# Sheet1.net
KiCad netlist of a schematic drawn in Altium Designer
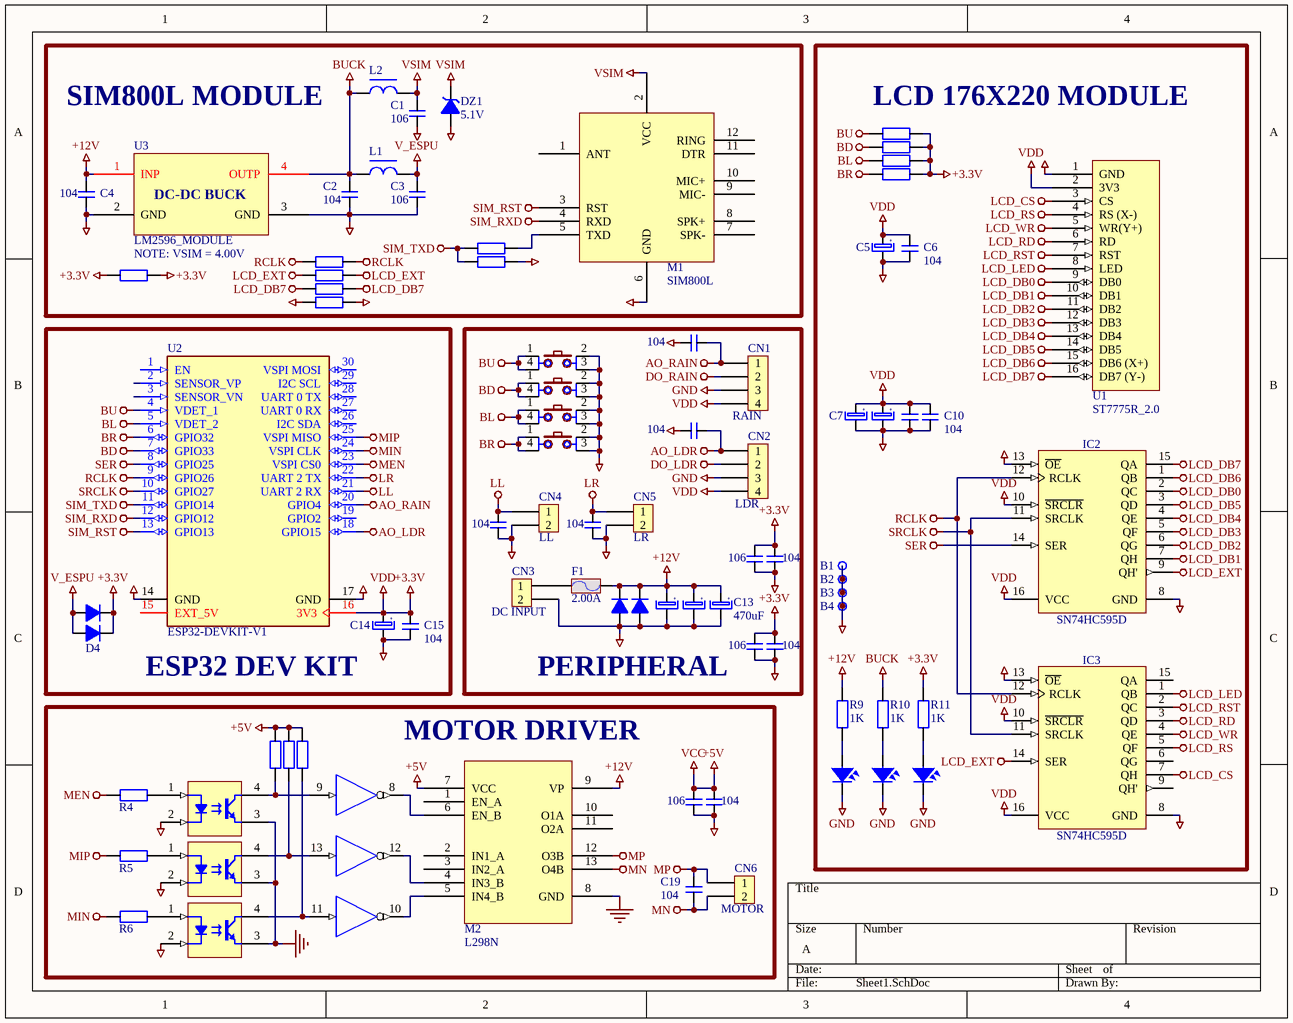
[diagram p0: Sheet1.SchDoc]

(export (version "E")
  (design (tool "Eeschema 10.0.6"))
  (components
    (comp (ref "B1")
      (value "Plated Hole")
      (footprint "MTG300_600")
      (description "Single Terminal Socket")
      (fields (field (name "PART NUMBER") "PLATED_HOLE3.0_PAD6.0") (field (name "AUTHOR") "CERN DEM JLC"))
      (libsource (lib "Eletro-mechanical") (part "Single Terminal Socket"))
    )
    (comp (ref "B2")
      (value "Plated Hole")
      (footprint "MTG300_600")
      (description "Single Terminal Socket")
      (fields (field (name "PART NUMBER") "PLATED_HOLE3.0_PAD6.0") (field (name "AUTHOR") "CERN DEM JLC"))
      (libsource (lib "Eletro-mechanical") (part "Single Terminal Socket"))
    )
    (comp (ref "B3")
      (value "Plated Hole")
      (footprint "MTG300_600")
      (description "Single Terminal Socket")
      (fields (field (name "PART NUMBER") "PLATED_HOLE3.0_PAD6.0") (field (name "AUTHOR") "CERN DEM JLC"))
      (libsource (lib "Eletro-mechanical") (part "Single Terminal Socket"))
    )
    (comp (ref "B4")
      (value "Plated Hole")
      (footprint "MTG300_600")
      (description "Single Terminal Socket")
      (fields (field (name "PART NUMBER") "PLATED_HOLE3.0_PAD6.0") (field (name "AUTHOR") "CERN DEM JLC"))
      (libsource (lib "Eletro-mechanical") (part "Single Terminal Socket"))
    )
    (comp (ref "C1")
      (value "106")
      (footprint "CAP-SMD-0805")
      (description "Non-polar capacitor")
      (libsource (lib "Library") (part "Cap-Non-SMD"))
    )
    (comp (ref "C2")
      (value "104")
      (footprint "Cap-Non-150mil")
      (description "Non-polar capacitor")
      (libsource (lib "Library") (part "Cap-Non-Dip"))
    )
    (comp (ref "C3")
      (value "106")
      (footprint "CAP-SMD-0805")
      (description "Non-polar capacitor")
      (libsource (lib "Library") (part "Cap-Non-SMD"))
    )
    (comp (ref "C4")
      (value "104")
      (footprint "Cap-Non-150mil")
      (description "Non-polar capacitor")
      (libsource (lib "Library") (part "Cap-Non-Dip"))
    )
    (comp (ref "C5")
      (value "220uF")
      (footprint "Cap-P-2.5/5")
      (description "Polarized capacitor")
      (libsource (lib "Library") (part "Cap-Pol-Dip"))
    )
    (comp (ref "C6")
      (value "104")
      (footprint "Cap-Non-150mil")
      (description "Non-polar capacitor")
      (libsource (lib "Library") (part "Cap-Non-Dip"))
    )
    (comp (ref "C7")
      (value "220uF")
      (footprint "Cap-P-2.5/5")
      (description "Polarized capacitor")
      (libsource (lib "Library") (part "Cap-Pol-Dip"))
    )
    (comp (ref "C8")
      (value "220uF")
      (footprint "Cap-P-2.5/5")
      (description "Polarized capacitor")
      (libsource (lib "Library") (part "Cap-Pol-Dip"))
    )
    (comp (ref "C9")
      (value "104")
      (footprint "Cap-Non-150mil")
      (description "Non-polar capacitor")
      (libsource (lib "Library") (part "Cap-Non-Dip"))
    )
    (comp (ref "C10")
      (value "104")
      (footprint "Cap-Non-150mil")
      (description "Non-polar capacitor")
      (libsource (lib "Library") (part "Cap-Non-Dip"))
    )
    (comp (ref "C11")
      (value "470uF")
      (footprint "Cap-P-3.8/6.3")
      (description "Polarized capacitor")
      (libsource (lib "Library") (part "Cap-Pol-Dip"))
    )
    (comp (ref "C12")
      (value "470uF")
      (footprint "Cap-P-3.8/6.3")
      (description "Polarized capacitor")
      (libsource (lib "Library") (part "Cap-Pol-Dip"))
    )
    (comp (ref "C13")
      (value "470uF")
      (footprint "Cap-P-3.8/6.3")
      (description "Polarized capacitor")
      (libsource (lib "Library") (part "Cap-Pol-Dip"))
    )
    (comp (ref "C14")
      (value "220uF")
      (footprint "Cap-P-2.5/5")
      (description "Polarized capacitor")
      (libsource (lib "Library") (part "Cap-Pol-Dip"))
    )
    (comp (ref "C15")
      (value "104")
      (footprint "Cap-Non-150mil")
      (description "Non-polar capacitor")
      (libsource (lib "Library") (part "Cap-Non-Dip"))
    )
    (comp (ref "C16")
      (value "106")
      (footprint "CAP-SMD-0805")
      (description "Non-polar capacitor")
      (libsource (lib "Library") (part "Cap-Non-SMD"))
    )
    (comp (ref "C17")
      (value "104")
      (footprint "CAP-SMD-0805")
      (description "Non-polar capacitor")
      (libsource (lib "Library") (part "Cap-Non-SMD"))
    )
    (comp (ref "C18")
      (value "104")
      (footprint "CAP-SMD-0805")
      (description "Non-polar capacitor")
      (libsource (lib "Library") (part "Cap-Non-SMD"))
    )
    (comp (ref "C19")
      (value "104")
      (footprint "CAP-SMD-0805")
      (description "Non-polar capacitor")
      (libsource (lib "Library") (part "Cap-Non-Dip"))
    )
    (comp (ref "C20")
      (value "104")
      (footprint "CAP-SMD-0805")
      (description "Non-polar capacitor")
      (libsource (lib "Library") (part "Cap-Non-SMD"))
    )
    (comp (ref "C21")
      (value "104")
      (footprint "CAP-SMD-0805")
      (description "Non-polar capacitor")
      (libsource (lib "Library") (part "Cap-Non-SMD"))
    )
    (comp (ref "C22")
      (value "104")
      (footprint "CAP-SMD-0805")
      (description "Non-polar capacitor")
      (libsource (lib "Library") (part "Cap-Non-SMD"))
    )
    (comp (ref "C23")
      (value "106")
      (footprint "CAP-SMD-0805")
      (description "Non-polar capacitor")
      (libsource (lib "Library") (part "Cap-Non-SMD"))
    )
    (comp (ref "C24")
      (value "104")
      (footprint "CAP-SMD-0805")
      (description "Non-polar capacitor")
      (libsource (lib "Library") (part "Cap-Non-SMD"))
    )
    (comp (ref "C25")
      (value "106")
      (footprint "CAP-SMD-0805")
      (description "Non-polar capacitor")
      (libsource (lib "Library") (part "Cap-Non-SMD"))
    )
    (comp (ref "C26")
      (value "104")
      (footprint "CAP-SMD-0805")
      (description "Non-polar capacitor")
      (libsource (lib "Library") (part "Cap-Non-SMD"))
    )
    (comp (ref "CN1") (value "RAIN") (footprint "Header 4P") (libsource (lib "Library") (part "Header 4")))
    (comp (ref "CN2") (value "LDR") (footprint "Header 4P") (libsource (lib "Library") (part "Header 4")))
    (comp (ref "CN3") (value "DC INPUT") (footprint "KF2/5.08") (libsource (lib "") (part "KF 2_1")))
    (comp (ref "CN4") (value "LL") (footprint "Header 2P") (libsource (lib "Library") (part "Header 2")))
    (comp (ref "CN5") (value "LR") (footprint "Header 2P") (libsource (lib "Library") (part "Header 2")))
    (comp (ref "CN6") (value "MOTOR") (footprint "KF2/5.08") (libsource (lib "Library") (part "KF 2")))
    (comp (ref "D1")
      (value "SS14")
      (footprint "SOD 106")
      (description "Diode SMD")
      (libsource (lib "Library") (part "Diode SMD"))
    )
    (comp (ref "D2")
      (value "SS14")
      (footprint "SOD 106")
      (description "Diode SMD")
      (libsource (lib "Library") (part "Diode SMD"))
    )
    (comp (ref "D3")
      (value "SS14")
      (footprint "SOD 106")
      (description "Diode SMD")
      (libsource (lib "Library") (part "Diode SMD"))
    )
    (comp (ref "D4")
      (value "SS14")
      (footprint "SOD 106")
      (description "Diode SMD")
      (libsource (lib "Library") (part "Diode SMD"))
    )
    (comp (ref "DZ1")
      (value "5.1V")
      (footprint "Diode-Zenner-200mil")
      (description "Diode Zenner")
      (libsource (lib "Library") (part "Diode Zenner"))
    )
    (comp (ref "F1") (value "2.00A") (footprint "Fuse-Dip1") (libsource (lib "Library") (part "Fuse Dip")))
    (comp (ref "IC1")
      (value "FOD817DSD")
      (footprint "DIP4")
      (description "Single Optocoupler")
      (fields (field (name "MANUFACTURER") "FAIRCHILD SEMICONDUCTOR") (field (name "AUTHOR") "CERN DEM JLC"))
      (libsource (lib "ICs And Semiconductors") (part "Optocoupler Type7"))
    )
    (comp (ref "IC2")
      (value "SN74HC595D")
      (footprint "SOIC127P600X175-16N")
      (description "8-Bit Shift Register With 3-State Output Register")
      (fields (field (name "MANUFACTURER") "TEXAS INSTRUMENTS") (field (name "AUTHOR") "CERN DEM JLC"))
      (libsource (lib "ICs And Semiconductors") (part "74595"))
    )
    (comp (ref "IC3")
      (value "SN74HC595D")
      (footprint "SOIC127P600X175-16N")
      (description "8-Bit Shift Register With 3-State Output Register")
      (fields (field (name "MANUFACTURER") "TEXAS INSTRUMENTS") (field (name "AUTHOR") "CERN DEM JLC"))
      (libsource (lib "ICs And Semiconductors") (part "74595"))
    )
    (comp (ref "IC4")
      (value "FOD817DSD")
      (footprint "DIP4")
      (description "Single Optocoupler")
      (fields (field (name "MANUFACTURER") "FAIRCHILD SEMICONDUCTOR") (field (name "AUTHOR") "CERN DEM JLC"))
      (libsource (lib "ICs And Semiconductors") (part "Optocoupler Type7"))
    )
    (comp (ref "IC5")
      (value "FOD817DSD")
      (footprint "DIP4")
      (description "Single Optocoupler")
      (fields (field (name "MANUFACTURER") "FAIRCHILD SEMICONDUCTOR") (field (name "AUTHOR") "CERN DEM JLC"))
      (libsource (lib "ICs And Semiconductors") (part "Optocoupler Type7"))
    )
    (comp (ref "IC6")
      (value "74HC14D")
      (footprint "SOIC127P600X175-14N")
      (description "Hex Schmitt-Trigger Inverter")
      (fields (field (name "MANUFACTURER") "NXP SEMICONDUCTORS") (field (name "AUTHOR") "CERN DEM JLC"))
      (libsource (lib "ICs And Semiconductors") (part "7414"))
    )
    (comp (ref "L1")
      (value "470uH")
      (footprint "L-DIP-M-5.3")
      (description "Inductor")
      (libsource (lib "Library") (part "IND-DIP-1"))
    )
    (comp (ref "L2")
      (value "470uH")
      (footprint "L-DIP-M-5.3")
      (description "Inductor")
      (libsource (lib "Library") (part "IND-DIP-1"))
    )
    (comp (ref "LED1") (value "POWER") (footprint "LED-0805") (libsource (lib "Library") (part "LED_SMD")))
    (comp (ref "LED2") (value "ESP-5.0V") (footprint "LED-0805") (libsource (lib "Library") (part "LED_SMD")))
    (comp (ref "LED3") (value "ESP-3.3V") (footprint "LED-0805") (libsource (lib "Library") (part "LED_SMD")))
    (comp (ref "M1")
      (value "SIM800L")
      (footprint "SIM800L_M")
      (libsource (lib "TOAN_VERSION_1_0") (part "SIM800L"))
    )
    (comp (ref "M2")
      (value "L298N")
      (footprint "L298N_MODULE")
      (libsource (lib "TOAN_VERSION_1_0") (part "L298N"))
    )
    (comp (ref "R1")
      (value "1K")
      (footprint "RES-SMD-0805")
      (description "Resistor 1/4W")
      (libsource (lib "Library") (part "Res 1/4W"))
    )
    (comp (ref "R2")
      (value "1K")
      (footprint "RES-SMD-0805")
      (description "Resistor 1/4W")
      (libsource (lib "Library") (part "Res 1/4W"))
    )
    (comp (ref "R3")
      (value "1K")
      (footprint "RES-SMD-0805")
      (description "Resistor 1/4W")
      (libsource (lib "Library") (part "Res 1/4W"))
    )
    (comp (ref "R4")
      (value "1K")
      (footprint "RES-SMD-0805")
      (description "Resistor 1/4W")
      (libsource (lib "Library") (part "Res 1/4W"))
    )
    (comp (ref "R5")
      (value "1K")
      (footprint "RES-SMD-0805")
      (description "Resistor 1/4W")
      (libsource (lib "Library") (part "Res 1/4W"))
    )
    (comp (ref "R6")
      (value "1K")
      (footprint "RES-SMD-0805")
      (description "Resistor 1/4W")
      (libsource (lib "Library") (part "Res 1/4W"))
    )
    (comp (ref "R7")
      (value "1K")
      (footprint "RES-SMD-0805")
      (description "Resistor 1/4W")
      (libsource (lib "Library") (part "Res 1/4W"))
    )
    (comp (ref "R8")
      (value "1K")
      (footprint "RES-SMD-0805")
      (description "Resistor 1/4W")
      (libsource (lib "Library") (part "Res 1/4W"))
    )
    (comp (ref "R9")
      (value "1K")
      (footprint "RES-SMD-0805")
      (description "Resistor 1/4W")
      (libsource (lib "Library") (part "Res 1/4W"))
    )
    (comp (ref "R10")
      (value "1K")
      (footprint "RES-SMD-0805")
      (description "Resistor 1/4W")
      (libsource (lib "Library") (part "Res 1/4W"))
    )
    (comp (ref "R11")
      (value "1K")
      (footprint "RES-SMD-0805")
      (description "Resistor 1/4W")
      (libsource (lib "Library") (part "Res 1/4W"))
    )
    (comp (ref "R13")
      (value "0R")
      (footprint "RES-SMD-0805")
      (description "Resistor SMD")
      (libsource (lib "Library") (part "Res SMD"))
    )
    (comp (ref "R14")
      (value "0R")
      (footprint "RES-SMD-0805")
      (description "Resistor SMD")
      (libsource (lib "Library") (part "Res SMD"))
    )
    (comp (ref "R15")
      (value "0R")
      (footprint "RES-SMD-0805")
      (description "Resistor SMD")
      (libsource (lib "Library") (part "Res SMD"))
    )
    (comp (ref "R16")
      (value "0R")
      (footprint "RES-SMD-1206")
      (description "Resistor SMD")
      (libsource (lib "Library") (part "Res SMD"))
    )
    (comp (ref "R17")
      (value "1K")
      (footprint "RES-SMD-0805")
      (description "Resistor 1/4W")
      (libsource (lib "Library") (part "Res 1/4W"))
    )
    (comp (ref "R21")
      (value "1K")
      (footprint "RES-SMD-0805")
      (description "Resistor 1/4W")
      (libsource (lib "Library") (part "Res 1/4W"))
    )
    (comp (ref "R22")
      (value "1K")
      (footprint "RES-SMD-0805")
      (description "Resistor 1/4W")
      (libsource (lib "Library") (part "Res 1/4W"))
    )
    (comp (ref "R23")
      (value "1K")
      (footprint "RES-SMD-0805")
      (description "Resistor 1/4W")
      (libsource (lib "Library") (part "Res 1/4W"))
    )
    (comp (ref "R27")
      (value "0R")
      (footprint "RES-SMD-1206")
      (description "Resistor 1/4W")
      (libsource (lib "Library") (part "Res 1/4W"))
    )
    (comp (ref "SW1")
      (value "UP")
      (footprint "Button-Dip4/6x6")
      (description "Switch button 4 pin")
      (libsource (lib "Library") (part "Button-4"))
    )
    (comp (ref "SW2")
      (value "DOWN")
      (footprint "Button-Dip4/6x6")
      (description "Switch button 4 pin")
      (libsource (lib "Library") (part "Button-4"))
    )
    (comp (ref "SW3")
      (value "LEFT")
      (footprint "Button-Dip4/6x6")
      (description "Switch button 4 pin")
      (libsource (lib "Library") (part "Button-4"))
    )
    (comp (ref "SW4")
      (value "RIGHT")
      (footprint "Button-Dip4/6x6")
      (description "Switch button 4 pin")
      (libsource (lib "Library") (part "Button-4"))
    )
    (comp (ref "U1")
      (value "ST7775R_2.0")
      (footprint "LCD_176X220_MODULE")
      (libsource (lib "TOAN_VERSION_1_0") (part "LCD_176x220_ST7775R"))
    )
    (comp (ref "U2")
      (value "ESP32-DEVKIT-V1")
      (footprint "MODULE_ESP32-DEVKITC-32D")
      (fields (field (name "MF") "Espressif Systems") (field (name "MP") "ESP32-DEVKITC-32D"))
      (libsource (lib "TOAN_VERSION_1_0") (part "ESP32-DEVKIT-V1"))
    )
    (comp (ref "U3")
      (value "LM2596_MODULE")
      (footprint "LM2596_MODULE")
      (libsource (lib "TOAN_VERSION_1_0") (part "LM2596_MODULE"))
    )
  )
  (nets
    (net (code "1") (name "+3.3V") (class "Default")
      (node (ref "C10") (pin "2") (pinfunction "2_2") (pintype "passive"))
      (node (ref "C14") (pin "1") (pinfunction "1_1") (pintype "passive"))
      (node (ref "C15") (pin "2") (pinfunction "2_2") (pintype "passive"))
      (node (ref "C23") (pin "2") (pinfunction "2_2") (pintype "passive"))
      (node (ref "C24") (pin "2") (pinfunction "2_2") (pintype "passive"))
      (node (ref "C25") (pin "2") (pinfunction "2_2") (pintype "passive"))
      (node (ref "C26") (pin "2") (pinfunction "2_2") (pintype "passive"))
      (node (ref "C5") (pin "1") (pinfunction "1_1") (pintype "passive"))
      (node (ref "C6") (pin "2") (pinfunction "2_2") (pintype "passive"))
      (node (ref "C7") (pin "1") (pinfunction "1_1") (pintype "passive"))
      (node (ref "C8") (pin "1") (pinfunction "1_1") (pintype "passive"))
      (node (ref "C9") (pin "2") (pinfunction "2_2") (pintype "passive"))
      (node (ref "CN1") (pin "4") (pinfunction "4_4") (pintype "passive"))
      (node (ref "CN2") (pin "4") (pinfunction "4_4") (pintype "passive"))
      (node (ref "D1") (pin "2") (pinfunction "K_2") (pintype "passive"))
      (node (ref "D4") (pin "2") (pinfunction "K_2") (pintype "passive"))
      (node (ref "IC2") (pin "10") (pinfunction "~{SRCLR}_10") (pintype "input"))
      (node (ref "IC2") (pin "16") (pinfunction "VCC_16") (pintype "power_in"))
      (node (ref "IC3") (pin "10") (pinfunction "~{SRCLR}_10") (pintype "input"))
      (node (ref "IC3") (pin "16") (pinfunction "VCC_16") (pintype "power_in"))
      (node (ref "R11") (pin "2") (pinfunction "2_2") (pintype "passive"))
      (node (ref "R17") (pin "1") (pinfunction "1_1") (pintype "passive"))
      (node (ref "R21") (pin "1") (pinfunction "1_1") (pintype "passive"))
      (node (ref "R22") (pin "1") (pinfunction "1_1") (pintype "passive"))
      (node (ref "R23") (pin "1") (pinfunction "1_1") (pintype "passive"))
      (node (ref "R27") (pin "1") (pinfunction "1_1") (pintype "passive"))
      (node (ref "R27") (pin "2") (pinfunction "2_2") (pintype "passive"))
      (node (ref "U1") (pin "2") (pinfunction "3V3_2") (pintype "power_in"))
      (node (ref "U2") (pin "16") (pinfunction "3V3_16") (pintype "power_in"))
    )
    (net (code "2") (name "+5V") (class "Default")
      (node (ref "C16") (pin "2") (pinfunction "2_2") (pintype "passive"))
      (node (ref "C17") (pin "2") (pinfunction "2_2") (pintype "passive"))
      (node (ref "IC6") (pin "14") (pinfunction "VCC_14") (pintype "power_in"))
      (node (ref "M2") (pin "7") (pinfunction "VCC_7") (pintype "passive"))
      (node (ref "R1") (pin "2") (pinfunction "2_2") (pintype "passive"))
      (node (ref "R2") (pin "2") (pinfunction "2_2") (pintype "passive"))
      (node (ref "R3") (pin "2") (pinfunction "2_2") (pintype "passive"))
    )
    (net (code "3") (name "+12V") (class "Default")
      (node (ref "C11") (pin "1") (pinfunction "1_1") (pintype "passive"))
      (node (ref "C12") (pin "1") (pinfunction "1_1") (pintype "passive"))
      (node (ref "C13") (pin "1") (pinfunction "1_1") (pintype "passive"))
      (node (ref "C4") (pin "1") (pinfunction "1_1") (pintype "passive"))
      (node (ref "D2") (pin "2") (pinfunction "K_2") (pintype "passive"))
      (node (ref "D3") (pin "2") (pinfunction "K_2") (pintype "passive"))
      (node (ref "F1") (pin "2") (pinfunction "2_2") (pintype "passive"))
      (node (ref "M2") (pin "9") (pinfunction "VP_9") (pintype "passive"))
      (node (ref "R9") (pin "2") (pinfunction "2_2") (pintype "passive"))
      (node (ref "U3") (pin "1") (pinfunction "INP_1") (pintype "power_in"))
    )
    (net (code "4") (name "AO_LDR") (class "Default")
      (node (ref "C22") (pin "1") (pinfunction "1_1") (pintype "passive"))
      (node (ref "CN2") (pin "1") (pinfunction "1_1") (pintype "passive"))
      (node (ref "U2") (pin "18") (pinfunction "GPIO15_18") (pintype "bidirectional"))
    )
    (net (code "5") (name "AO_RAIN") (class "Default")
      (node (ref "C21") (pin "1") (pinfunction "1_1") (pintype "passive"))
      (node (ref "CN1") (pin "1") (pinfunction "1_1") (pintype "passive"))
      (node (ref "U2") (pin "20") (pinfunction "GPIO4_20") (pintype "bidirectional"))
    )
    (net (code "6") (name "BD") (class "Default")
      (node (ref "R17") (pin "2") (pinfunction "2_2") (pintype "passive"))
      (node (ref "SW2") (pin "1") (pintype "passive"))
      (node (ref "SW2") (pin "4") (pinfunction "4_4") (pintype "passive"))
      (node (ref "U2") (pin "7") (pinfunction "GPIO33_7") (pintype "bidirectional"))
    )
    (net (code "7") (name "BL") (class "Default")
      (node (ref "R22") (pin "2") (pinfunction "2_2") (pintype "passive"))
      (node (ref "SW3") (pin "1") (pintype "passive"))
      (node (ref "SW3") (pin "4") (pinfunction "4_4") (pintype "passive"))
      (node (ref "U2") (pin "5") (pinfunction "VDET_2_5") (pintype "input"))
    )
    (net (code "8") (name "BR") (class "Default")
      (node (ref "R21") (pin "2") (pinfunction "2_2") (pintype "passive"))
      (node (ref "SW4") (pin "1") (pintype "passive"))
      (node (ref "SW4") (pin "4") (pinfunction "4_4") (pintype "passive"))
      (node (ref "U2") (pin "6") (pinfunction "GPIO32_6") (pintype "bidirectional"))
    )
    (net (code "9") (name "BU") (class "Default")
      (node (ref "R23") (pin "2") (pinfunction "2_2") (pintype "passive"))
      (node (ref "SW1") (pin "1") (pintype "passive"))
      (node (ref "SW1") (pin "4") (pinfunction "4_4") (pintype "passive"))
      (node (ref "U2") (pin "4") (pinfunction "VDET_1_4") (pintype "input"))
    )
    (net (code "10") (name "BUCK") (class "Default")
      (node (ref "C2") (pin "1") (pinfunction "1_1") (pintype "passive"))
      (node (ref "L1") (pin "1") (pinfunction "1_1") (pintype "passive"))
      (node (ref "L2") (pin "1") (pinfunction "1_1") (pintype "passive"))
      (node (ref "R10") (pin "2") (pinfunction "2_2") (pintype "passive"))
      (node (ref "U3") (pin "4") (pinfunction "OUTP_4") (pintype "power_in"))
    )
    (net (code "11") (name "DO_LDR") (class "Default")
      (node (ref "CN2") (pin "2") (pinfunction "2_2") (pintype "passive"))
    )
    (net (code "12") (name "DO_RAIN") (class "Default")
      (node (ref "CN1") (pin "2") (pinfunction "2_2") (pintype "passive"))
    )
    (net (code "13") (name "GND") (class "Default")
      (node (ref "B1") (pin "1") (pinfunction "1_1") (pintype "bidirectional"))
      (node (ref "B2") (pin "1") (pinfunction "1_1") (pintype "bidirectional"))
      (node (ref "B3") (pin "1") (pinfunction "1_1") (pintype "bidirectional"))
      (node (ref "B4") (pin "1") (pinfunction "1_1") (pintype "bidirectional"))
      (node (ref "C1") (pin "1") (pinfunction "1_1") (pintype "passive"))
      (node (ref "C10") (pin "1") (pinfunction "1_1") (pintype "passive"))
      (node (ref "C11") (pin "2") (pinfunction "2_2") (pintype "passive"))
      (node (ref "C12") (pin "2") (pinfunction "2_2") (pintype "passive"))
      (node (ref "C13") (pin "2") (pinfunction "2_2") (pintype "passive"))
      (node (ref "C14") (pin "2") (pinfunction "2_2") (pintype "passive"))
      (node (ref "C15") (pin "1") (pinfunction "1_1") (pintype "passive"))
      (node (ref "C16") (pin "1") (pinfunction "1_1") (pintype "passive"))
      (node (ref "C17") (pin "1") (pinfunction "1_1") (pintype "passive"))
      (node (ref "C18") (pin "2") (pinfunction "2_2") (pintype "passive"))
      (node (ref "C2") (pin "2") (pinfunction "2_2") (pintype "passive"))
      (node (ref "C20") (pin "2") (pinfunction "2_2") (pintype "passive"))
      (node (ref "C21") (pin "2") (pinfunction "2_2") (pintype "passive"))
      (node (ref "C22") (pin "2") (pinfunction "2_2") (pintype "passive"))
      (node (ref "C23") (pin "1") (pinfunction "1_1") (pintype "passive"))
      (node (ref "C24") (pin "1") (pinfunction "1_1") (pintype "passive"))
      (node (ref "C25") (pin "1") (pinfunction "1_1") (pintype "passive"))
      (node (ref "C26") (pin "1") (pinfunction "1_1") (pintype "passive"))
      (node (ref "C3") (pin "1") (pinfunction "1_1") (pintype "passive"))
      (node (ref "C4") (pin "2") (pinfunction "2_2") (pintype "passive"))
      (node (ref "C5") (pin "2") (pinfunction "2_2") (pintype "passive"))
      (node (ref "C6") (pin "1") (pinfunction "1_1") (pintype "passive"))
      (node (ref "C7") (pin "2") (pinfunction "2_2") (pintype "passive"))
      (node (ref "C8") (pin "2") (pinfunction "2_2") (pintype "passive"))
      (node (ref "C9") (pin "1") (pinfunction "1_1") (pintype "passive"))
      (node (ref "CN1") (pin "3") (pinfunction "3_3") (pintype "passive"))
      (node (ref "CN2") (pin "3") (pinfunction "3_3") (pintype "passive"))
      (node (ref "CN3") (pin "2") (pinfunction "2_2") (pintype "passive"))
      (node (ref "CN4") (pin "2") (pinfunction "2_2") (pintype "passive"))
      (node (ref "CN5") (pin "2") (pinfunction "2_2") (pintype "passive"))
      (node (ref "D2") (pin "1") (pinfunction "A_1") (pintype "passive"))
      (node (ref "D3") (pin "1") (pinfunction "A_1") (pintype "passive"))
      (node (ref "DZ1") (pin "1") (pinfunction "A_1") (pintype "passive"))
      (node (ref "IC1") (pin "2") (pinfunction "C_2") (pintype "input"))
      (node (ref "IC1") (pin "3") (pinfunction "E_3") (pintype "open_emitter"))
      (node (ref "IC2") (pin "13") (pinfunction "~{OE}_13") (pintype "input"))
      (node (ref "IC2") (pin "8") (pinfunction "GND_8") (pintype "power_in"))
      (node (ref "IC3") (pin "13") (pinfunction "~{OE}_13") (pintype "input"))
      (node (ref "IC3") (pin "8") (pinfunction "GND_8") (pintype "power_in"))
      (node (ref "IC4") (pin "2") (pinfunction "C_2") (pintype "input"))
      (node (ref "IC4") (pin "3") (pinfunction "E_3") (pintype "open_emitter"))
      (node (ref "IC5") (pin "2") (pinfunction "C_2") (pintype "input"))
      (node (ref "IC5") (pin "3") (pinfunction "E_3") (pintype "open_emitter"))
      (node (ref "IC6") (pin "7") (pinfunction "GND_7") (pintype "power_in"))
      (node (ref "LED1") (pin "2") (pinfunction "2_2") (pintype "passive"))
      (node (ref "LED2") (pin "2") (pinfunction "2_2") (pintype "passive"))
      (node (ref "LED3") (pin "2") (pinfunction "2_2") (pintype "passive"))
      (node (ref "M1") (pin "6") (pinfunction "GND_6") (pintype "passive"))
      (node (ref "M2") (pin "8") (pinfunction "GND_8") (pintype "passive"))
      (node (ref "R16") (pin "1") (pinfunction "1_1") (pintype "passive"))
      (node (ref "R16") (pin "2") (pinfunction "2_2") (pintype "passive"))
      (node (ref "R8") (pin "1") (pinfunction "1_1") (pintype "passive"))
      (node (ref "SW1") (pin "2") (pinfunction "2_2") (pintype "passive"))
      (node (ref "SW1") (pin "3") (pinfunction "3_3") (pintype "passive"))
      (node (ref "SW2") (pin "2") (pinfunction "2_2") (pintype "passive"))
      (node (ref "SW2") (pin "3") (pinfunction "3_3") (pintype "passive"))
      (node (ref "SW3") (pin "2") (pinfunction "2_2") (pintype "passive"))
      (node (ref "SW3") (pin "3") (pinfunction "3_3") (pintype "passive"))
      (node (ref "SW4") (pin "2") (pinfunction "2_2") (pintype "passive"))
      (node (ref "SW4") (pin "3") (pinfunction "3_3") (pintype "passive"))
      (node (ref "U1") (pin "1") (pinfunction "GND_1") (pintype "power_in"))
      (node (ref "U2") (pin "14") (pinfunction "GND_14") (pintype "power_in"))
      (node (ref "U2") (pin "17") (pinfunction "GND_17") (pintype "power_in"))
      (node (ref "U3") (pin "2") (pinfunction "GND_2") (pintype "power_in"))
      (node (ref "U3") (pin "3") (pinfunction "GND_3") (pintype "power_in"))
    )
    (net (code "14") (name "LCD_CS") (class "Default")
      (node (ref "IC3") (pin "7") (pinfunction "QH_7") (pintype "tri_state"))
      (node (ref "U1") (pin "3") (pinfunction "CS_3") (pintype "input"))
    )
    (net (code "15") (name "LCD_DB0") (class "Default")
      (node (ref "IC2") (pin "2") (pinfunction "QC_2") (pintype "tri_state"))
      (node (ref "U1") (pin "9") (pinfunction "DB0_9") (pintype "bidirectional"))
    )
    (net (code "16") (name "LCD_DB1") (class "Default")
      (node (ref "IC2") (pin "7") (pinfunction "QH_7") (pintype "tri_state"))
      (node (ref "U1") (pin "10") (pinfunction "DB1_10") (pintype "bidirectional"))
    )
    (net (code "17") (name "LCD_DB2") (class "Default")
      (node (ref "IC2") (pin "6") (pinfunction "QG_6") (pintype "tri_state"))
      (node (ref "U1") (pin "11") (pinfunction "DB2_11") (pintype "bidirectional"))
    )
    (net (code "18") (name "LCD_DB3") (class "Default")
      (node (ref "IC2") (pin "5") (pinfunction "QF_5") (pintype "tri_state"))
      (node (ref "U1") (pin "12") (pinfunction "DB3_12") (pintype "bidirectional"))
    )
    (net (code "19") (name "LCD_DB4") (class "Default")
      (node (ref "IC2") (pin "4") (pinfunction "QE_4") (pintype "tri_state"))
      (node (ref "U1") (pin "13") (pinfunction "DB4_13") (pintype "bidirectional"))
    )
    (net (code "20") (name "LCD_DB5") (class "Default")
      (node (ref "IC2") (pin "3") (pinfunction "QD_3") (pintype "tri_state"))
      (node (ref "U1") (pin "14") (pinfunction "DB5_14") (pintype "bidirectional"))
    )
    (net (code "21") (name "LCD_DB6") (class "Default")
      (node (ref "IC2") (pin "1") (pinfunction "QB_1") (pintype "tri_state"))
      (node (ref "U1") (pin "15") (pinfunction "DB6_(X+)_15") (pintype "bidirectional"))
    )
    (net (code "22") (name "LCD_DB7") (class "Default")
      (node (ref "IC2") (pin "15") (pinfunction "QA_15") (pintype "tri_state"))
      (node (ref "R15") (pin "1") (pinfunction "1_1") (pintype "passive"))
      (node (ref "R15") (pin "2") (pinfunction "2_2") (pintype "passive"))
      (node (ref "U1") (pin "16") (pinfunction "DB7_(Y-)_16") (pintype "bidirectional"))
    )
    (net (code "23") (name "LCD_EXT") (class "Default")
      (node (ref "IC2") (pin "9") (pinfunction "QH'_9") (pintype "output"))
      (node (ref "IC3") (pin "14") (pinfunction "SER_14") (pintype "input"))
      (node (ref "R14") (pin "1") (pinfunction "1_1") (pintype "passive"))
      (node (ref "R14") (pin "2") (pinfunction "2_2") (pintype "passive"))
    )
    (net (code "24") (name "LCD_LED") (class "Default")
      (node (ref "IC3") (pin "1") (pinfunction "QB_1") (pintype "tri_state"))
      (node (ref "U1") (pin "8") (pinfunction "LED_8") (pintype "input"))
    )
    (net (code "25") (name "LCD_RD") (class "Default")
      (node (ref "IC3") (pin "3") (pinfunction "QD_3") (pintype "tri_state"))
      (node (ref "U1") (pin "6") (pinfunction "RD_6") (pintype "input"))
    )
    (net (code "26") (name "LCD_RS") (class "Default")
      (node (ref "IC3") (pin "5") (pinfunction "QF_5") (pintype "tri_state"))
      (node (ref "U1") (pin "4") (pinfunction "RS_(X-)_4") (pintype "input"))
    )
    (net (code "27") (name "LCD_RST") (class "Default")
      (node (ref "IC3") (pin "2") (pinfunction "QC_2") (pintype "tri_state"))
      (node (ref "U1") (pin "7") (pinfunction "RST_7") (pintype "input"))
    )
    (net (code "28") (name "LCD_WR") (class "Default")
      (node (ref "IC3") (pin "4") (pinfunction "QE_4") (pintype "tri_state"))
      (node (ref "U1") (pin "5") (pinfunction "WR(Y+)_5") (pintype "input"))
    )
    (net (code "29") (name "LL") (class "Default")
      (node (ref "C18") (pin "1") (pinfunction "1_1") (pintype "passive"))
      (node (ref "CN4") (pin "1") (pinfunction "1_1") (pintype "passive"))
      (node (ref "U2") (pin "21") (pinfunction "UART_2_RX_21") (pintype "bidirectional"))
    )
    (net (code "30") (name "LR") (class "Default")
      (node (ref "C20") (pin "1") (pinfunction "1_1") (pintype "passive"))
      (node (ref "CN5") (pin "1") (pinfunction "1_1") (pintype "passive"))
      (node (ref "U2") (pin "22") (pinfunction "UART_2_TX_22") (pintype "bidirectional"))
    )
    (net (code "31") (name "MEN") (class "Default")
      (node (ref "R4") (pin "2") (pinfunction "2_2") (pintype "passive"))
      (node (ref "U2") (pin "23") (pinfunction "VSPI_CS0_23") (pintype "bidirectional"))
    )
    (net (code "32") (name "MIN") (class "Default")
      (node (ref "R6") (pin "2") (pinfunction "2_2") (pintype "passive"))
      (node (ref "U2") (pin "24") (pinfunction "VSPI_CLK_24") (pintype "bidirectional"))
    )
    (net (code "33") (name "MIP") (class "Default")
      (node (ref "R5") (pin "2") (pinfunction "2_2") (pintype "passive"))
      (node (ref "U2") (pin "25") (pinfunction "VSPI_MISO_25") (pintype "bidirectional"))
    )
    (net (code "34") (name "MN") (class "Default")
      (node (ref "C19") (pin "1") (pinfunction "1_1") (pintype "passive"))
      (node (ref "CN6") (pin "2") (pinfunction "2_2") (pintype "passive"))
      (node (ref "M2") (pin "13") (pinfunction "O4B_13") (pintype "passive"))
    )
    (net (code "35") (name "MP") (class "Default")
      (node (ref "C19") (pin "2") (pinfunction "2_2") (pintype "passive"))
      (node (ref "CN6") (pin "1") (pinfunction "1_1") (pintype "passive"))
      (node (ref "M2") (pin "12") (pinfunction "O3B_12") (pintype "passive"))
    )
    (net (code "36") (name "Net-(CN3-Pad1)") (class "Default")
      (node (ref "CN3") (pin "1") (pinfunction "1_1") (pintype "passive"))
      (node (ref "F1") (pin "1") (pinfunction "1_1") (pintype "passive"))
    )
    (net (code "37") (name "Net-(IC1-A)") (class "Default")
      (node (ref "IC1") (pin "1") (pinfunction "A_1") (pintype "input"))
      (node (ref "R4") (pin "1") (pinfunction "1_1") (pintype "passive"))
    )
    (net (code "38") (name "Net-(IC4-A)") (class "Default")
      (node (ref "IC4") (pin "1") (pinfunction "A_1") (pintype "input"))
      (node (ref "R5") (pin "1") (pinfunction "1_1") (pintype "passive"))
    )
    (net (code "39") (name "Net-(IC5-A)") (class "Default")
      (node (ref "IC5") (pin "1") (pinfunction "A_1") (pintype "input"))
      (node (ref "R6") (pin "1") (pinfunction "1_1") (pintype "passive"))
    )
    (net (code "40") (name "Net-(IC6D-IN)") (class "Default")
      (node (ref "IC1") (pin "4") (pinfunction "C_4") (pintype "open_collector"))
      (node (ref "IC6") (pin "9") (pinfunction "IN_9") (pintype "input"))
      (node (ref "R1") (pin "1") (pinfunction "1_1") (pintype "passive"))
    )
    (net (code "41") (name "Net-(IC6D-OUT)") (class "Default")
      (node (ref "IC6") (pin "8") (pinfunction "OUT_8") (pintype "output"))
      (node (ref "M2") (pin "6") (pinfunction "EN_B_6") (pintype "passive"))
    )
    (net (code "42") (name "Net-(IC6E-IN)") (class "Default")
      (node (ref "IC5") (pin "4") (pinfunction "C_4") (pintype "open_collector"))
      (node (ref "IC6") (pin "11") (pinfunction "IN_11") (pintype "input"))
      (node (ref "R3") (pin "1") (pinfunction "1_1") (pintype "passive"))
    )
    (net (code "43") (name "Net-(IC6E-OUT)") (class "Default")
      (node (ref "IC6") (pin "10") (pinfunction "OUT_10") (pintype "output"))
      (node (ref "M2") (pin "5") (pinfunction "IN4_B_5") (pintype "passive"))
    )
    (net (code "44") (name "Net-(IC6F-IN)") (class "Default")
      (node (ref "IC4") (pin "4") (pinfunction "C_4") (pintype "open_collector"))
      (node (ref "IC6") (pin "13") (pinfunction "IN_13") (pintype "input"))
      (node (ref "R2") (pin "1") (pinfunction "1_1") (pintype "passive"))
    )
    (net (code "45") (name "Net-(IC6F-OUT)") (class "Default")
      (node (ref "IC6") (pin "12") (pinfunction "OUT_12") (pintype "output"))
      (node (ref "M2") (pin "4") (pinfunction "IN3_B_4") (pintype "passive"))
    )
    (net (code "46") (name "Net-(LED1-Pad1)") (class "Default")
      (node (ref "LED1") (pin "1") (pinfunction "1_1") (pintype "passive"))
      (node (ref "R9") (pin "1") (pinfunction "1_1") (pintype "passive"))
    )
    (net (code "47") (name "Net-(LED2-Pad1)") (class "Default")
      (node (ref "LED2") (pin "1") (pinfunction "1_1") (pintype "passive"))
      (node (ref "R10") (pin "1") (pinfunction "1_1") (pintype "passive"))
    )
    (net (code "48") (name "Net-(LED3-Pad1)") (class "Default")
      (node (ref "LED3") (pin "1") (pinfunction "1_1") (pintype "passive"))
      (node (ref "R11") (pin "1") (pinfunction "1_1") (pintype "passive"))
    )
    (net (code "49") (name "Net-(M1-TXD)") (class "Default")
      (node (ref "M1") (pin "5") (pinfunction "TXD_5") (pintype "passive"))
      (node (ref "R7") (pin "2") (pinfunction "2_2") (pintype "passive"))
    )
    (net (code "50") (name "RCLK") (class "Default")
      (node (ref "IC2") (pin "12") (pinfunction "RCLK_12") (pintype "input"))
      (node (ref "IC3") (pin "12") (pinfunction "RCLK_12") (pintype "input"))
      (node (ref "R13") (pin "1") (pinfunction "1_1") (pintype "passive"))
      (node (ref "R13") (pin "2") (pinfunction "2_2") (pintype "passive"))
      (node (ref "U2") (pin "9") (pinfunction "GPIO26_9") (pintype "bidirectional"))
    )
    (net (code "51") (name "SER") (class "Default")
      (node (ref "IC2") (pin "14") (pinfunction "SER_14") (pintype "input"))
      (node (ref "U2") (pin "8") (pinfunction "GPIO25_8") (pintype "bidirectional"))
    )
    (net (code "52") (name "SIM_RST") (class "Default")
      (node (ref "M1") (pin "3") (pinfunction "RST_3") (pintype "passive"))
      (node (ref "U2") (pin "13") (pinfunction "GPIO13_13") (pintype "bidirectional"))
    )
    (net (code "53") (name "SIM_RXD") (class "Default")
      (node (ref "M1") (pin "4") (pinfunction "RXD_4") (pintype "passive"))
      (node (ref "U2") (pin "12") (pinfunction "GPIO12_12") (pintype "bidirectional"))
    )
    (net (code "54") (name "SIM_TXD") (class "Default")
      (node (ref "R7") (pin "1") (pinfunction "1_1") (pintype "passive"))
      (node (ref "R8") (pin "2") (pinfunction "2_2") (pintype "passive"))
      (node (ref "U2") (pin "11") (pinfunction "GPIO14_11") (pintype "bidirectional"))
    )
    (net (code "55") (name "SRCLK") (class "Default")
      (node (ref "IC2") (pin "11") (pinfunction "SRCLK_11") (pintype "input"))
      (node (ref "IC3") (pin "11") (pinfunction "SRCLK_11") (pintype "input"))
      (node (ref "U2") (pin "10") (pinfunction "GPIO27_10") (pintype "bidirectional"))
    )
    (net (code "56") (name "VSIM") (class "Default")
      (node (ref "C1") (pin "2") (pinfunction "2_2") (pintype "passive"))
      (node (ref "DZ1") (pin "2") (pinfunction "K_2") (pintype "passive"))
      (node (ref "L2") (pin "2") (pinfunction "2_2") (pintype "passive"))
      (node (ref "M1") (pin "2") (pinfunction "VCC_2") (pintype "passive"))
    )
    (net (code "57") (name "V_ESPU") (class "Default")
      (node (ref "C3") (pin "2") (pinfunction "2_2") (pintype "passive"))
      (node (ref "D1") (pin "1") (pinfunction "A_1") (pintype "passive"))
      (node (ref "D4") (pin "1") (pinfunction "A_1") (pintype "passive"))
      (node (ref "L1") (pin "2") (pinfunction "2_2") (pintype "passive"))
    )
    (net (code "58") (name "unconnected-(IC3-QA-Pad15)") (class "Default")
      (node (ref "IC3") (pin "15") (pinfunction "QA_15") (pintype "tri_state"))
    )
    (net (code "59") (name "unconnected-(IC3-QG-Pad6)") (class "Default")
      (node (ref "IC3") (pin "6") (pinfunction "QG_6") (pintype "tri_state"))
    )
    (net (code "60") (name "unconnected-(IC3-QH'-Pad9)") (class "Default")
      (node (ref "IC3") (pin "9") (pinfunction "QH'_9") (pintype "output"))
    )
    (net (code "61") (name "unconnected-(M1-ANT-Pad1)") (class "Default")
      (node (ref "M1") (pin "1") (pinfunction "ANT_1") (pintype "passive"))
    )
    (net (code "62") (name "unconnected-(M1-DTR-Pad11)") (class "Default")
      (node (ref "M1") (pin "11") (pinfunction "DTR_11") (pintype "passive"))
    )
    (net (code "63") (name "unconnected-(M1-MIC+-Pad10)") (class "Default")
      (node (ref "M1") (pin "10") (pinfunction "MIC+_10") (pintype "passive"))
    )
    (net (code "64") (name "unconnected-(M1-MIC--Pad9)") (class "Default")
      (node (ref "M1") (pin "9") (pinfunction "MIC-_9") (pintype "passive"))
    )
    (net (code "65") (name "unconnected-(M1-RING-Pad12)") (class "Default")
      (node (ref "M1") (pin "12") (pinfunction "RING_12") (pintype "passive"))
    )
    (net (code "66") (name "unconnected-(M1-SPK+-Pad8)") (class "Default")
      (node (ref "M1") (pin "8") (pinfunction "SPK+_8") (pintype "passive"))
    )
    (net (code "67") (name "unconnected-(M1-SPK--Pad7)") (class "Default")
      (node (ref "M1") (pin "7") (pinfunction "SPK-_7") (pintype "passive"))
    )
    (net (code "68") (name "unconnected-(M2-EN_A-Pad1)") (class "Default")
      (node (ref "M2") (pin "1") (pinfunction "EN_A_1") (pintype "passive"))
    )
    (net (code "69") (name "unconnected-(M2-IN1_A-Pad2)") (class "Default")
      (node (ref "M2") (pin "2") (pinfunction "IN1_A_2") (pintype "passive"))
    )
    (net (code "70") (name "unconnected-(M2-IN2_A-Pad3)") (class "Default")
      (node (ref "M2") (pin "3") (pinfunction "IN2_A_3") (pintype "passive"))
    )
    (net (code "71") (name "unconnected-(M2-O1A-Pad10)") (class "Default")
      (node (ref "M2") (pin "10") (pinfunction "O1A_10") (pintype "passive"))
    )
    (net (code "72") (name "unconnected-(M2-O2A-Pad11)") (class "Default")
      (node (ref "M2") (pin "11") (pinfunction "O2A_11") (pintype "passive"))
    )
    (net (code "73") (name "unconnected-(U2-EN-Pad1)") (class "Default")
      (node (ref "U2") (pin "1") (pinfunction "EN_1") (pintype "input"))
    )
    (net (code "74") (name "unconnected-(U2-EXT_5V-Pad15)") (class "Default")
      (node (ref "U2") (pin "15") (pinfunction "EXT_5V_15") (pintype "power_in"))
    )
    (net (code "75") (name "unconnected-(U2-GPIO2-Pad19)") (class "Default")
      (node (ref "U2") (pin "19") (pinfunction "GPIO2_19") (pintype "bidirectional"))
    )
    (net (code "76") (name "unconnected-(U2-I2C_SCL-Pad29)") (class "Default")
      (node (ref "U2") (pin "29") (pinfunction "I2C_SCL_29") (pintype "bidirectional"))
    )
    (net (code "77") (name "unconnected-(U2-I2C_SDA-Pad26)") (class "Default")
      (node (ref "U2") (pin "26") (pinfunction "I2C_SDA_26") (pintype "bidirectional"))
    )
    (net (code "78") (name "unconnected-(U2-SENSOR_VN-Pad3)") (class "Default")
      (node (ref "U2") (pin "3") (pinfunction "SENSOR_VN_3") (pintype "input"))
    )
    (net (code "79") (name "unconnected-(U2-SENSOR_VP-Pad2)") (class "Default")
      (node (ref "U2") (pin "2") (pinfunction "SENSOR_VP_2") (pintype "input"))
    )
    (net (code "80") (name "unconnected-(U2-UART_0_RX-Pad27)") (class "Default")
      (node (ref "U2") (pin "27") (pinfunction "UART_0_RX_27") (pintype "bidirectional"))
    )
    (net (code "81") (name "unconnected-(U2-UART_0_TX-Pad28)") (class "Default")
      (node (ref "U2") (pin "28") (pinfunction "UART_0_TX_28") (pintype "bidirectional"))
    )
    (net (code "82") (name "unconnected-(U2-VSPI_MOSI-Pad30)") (class "Default")
      (node (ref "U2") (pin "30") (pinfunction "VSPI_MOSI_30") (pintype "bidirectional"))
    )
  )
)
